# devbrd.net
KiCad netlist of a schematic drawn in EAGLE
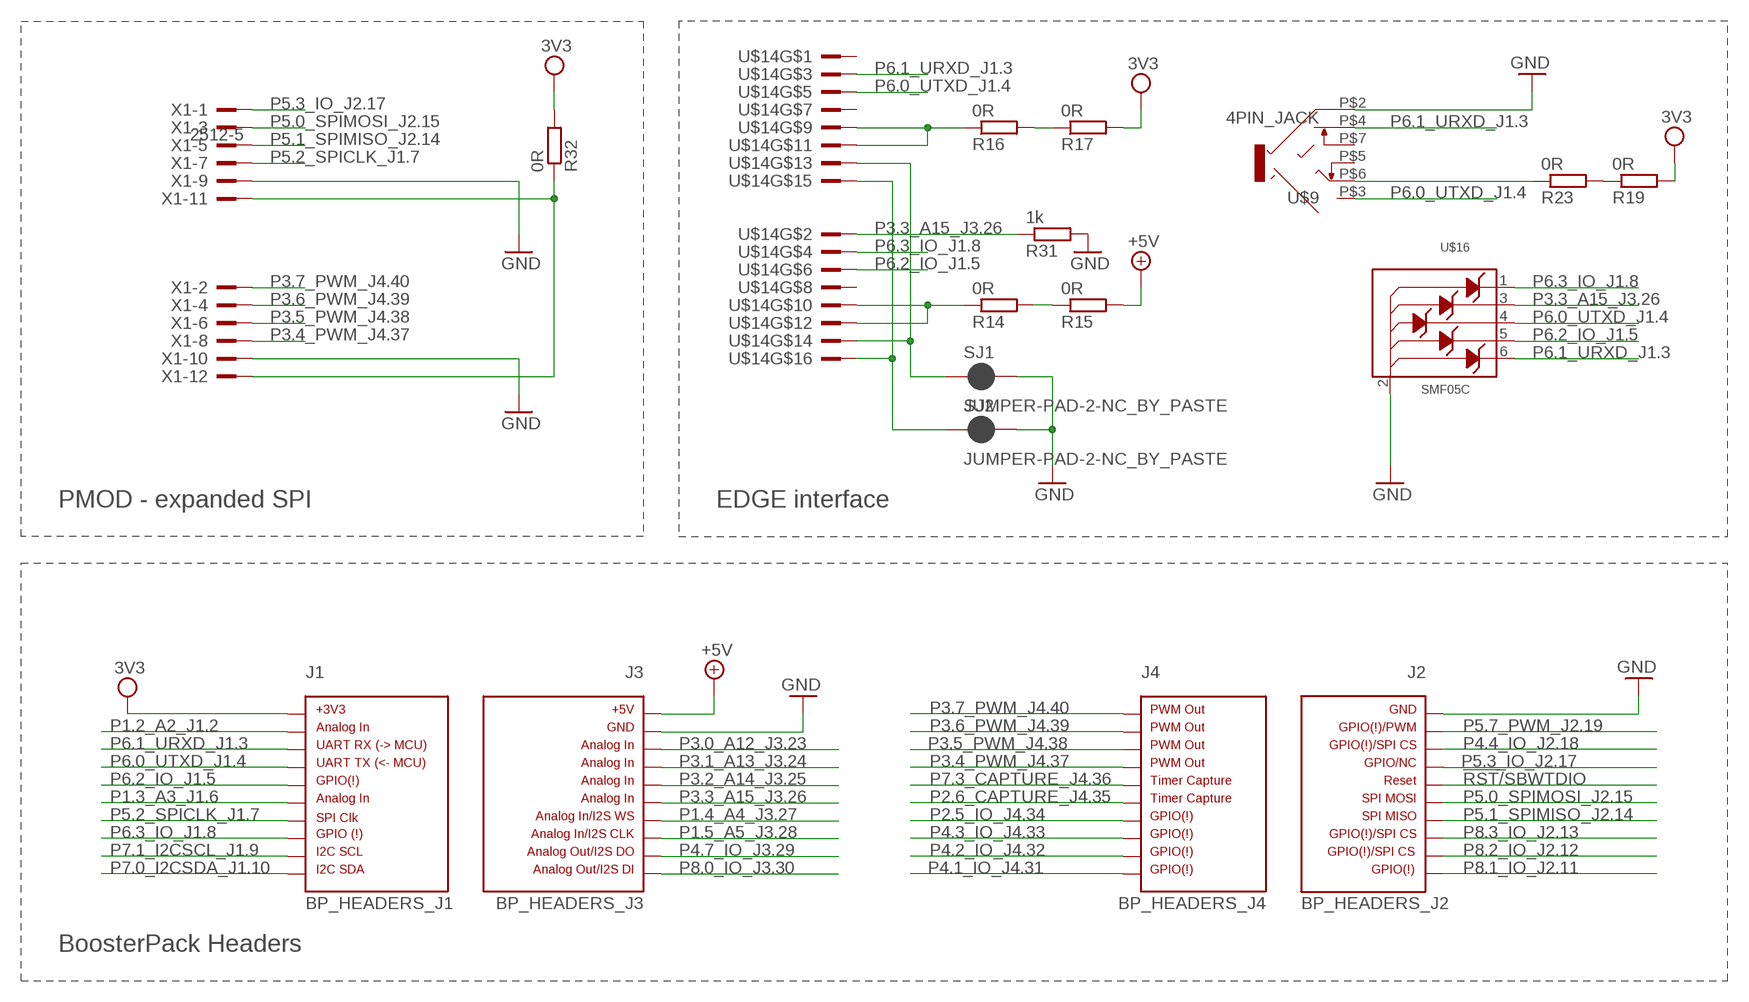
[diagram p0: schematic, sheet 1]
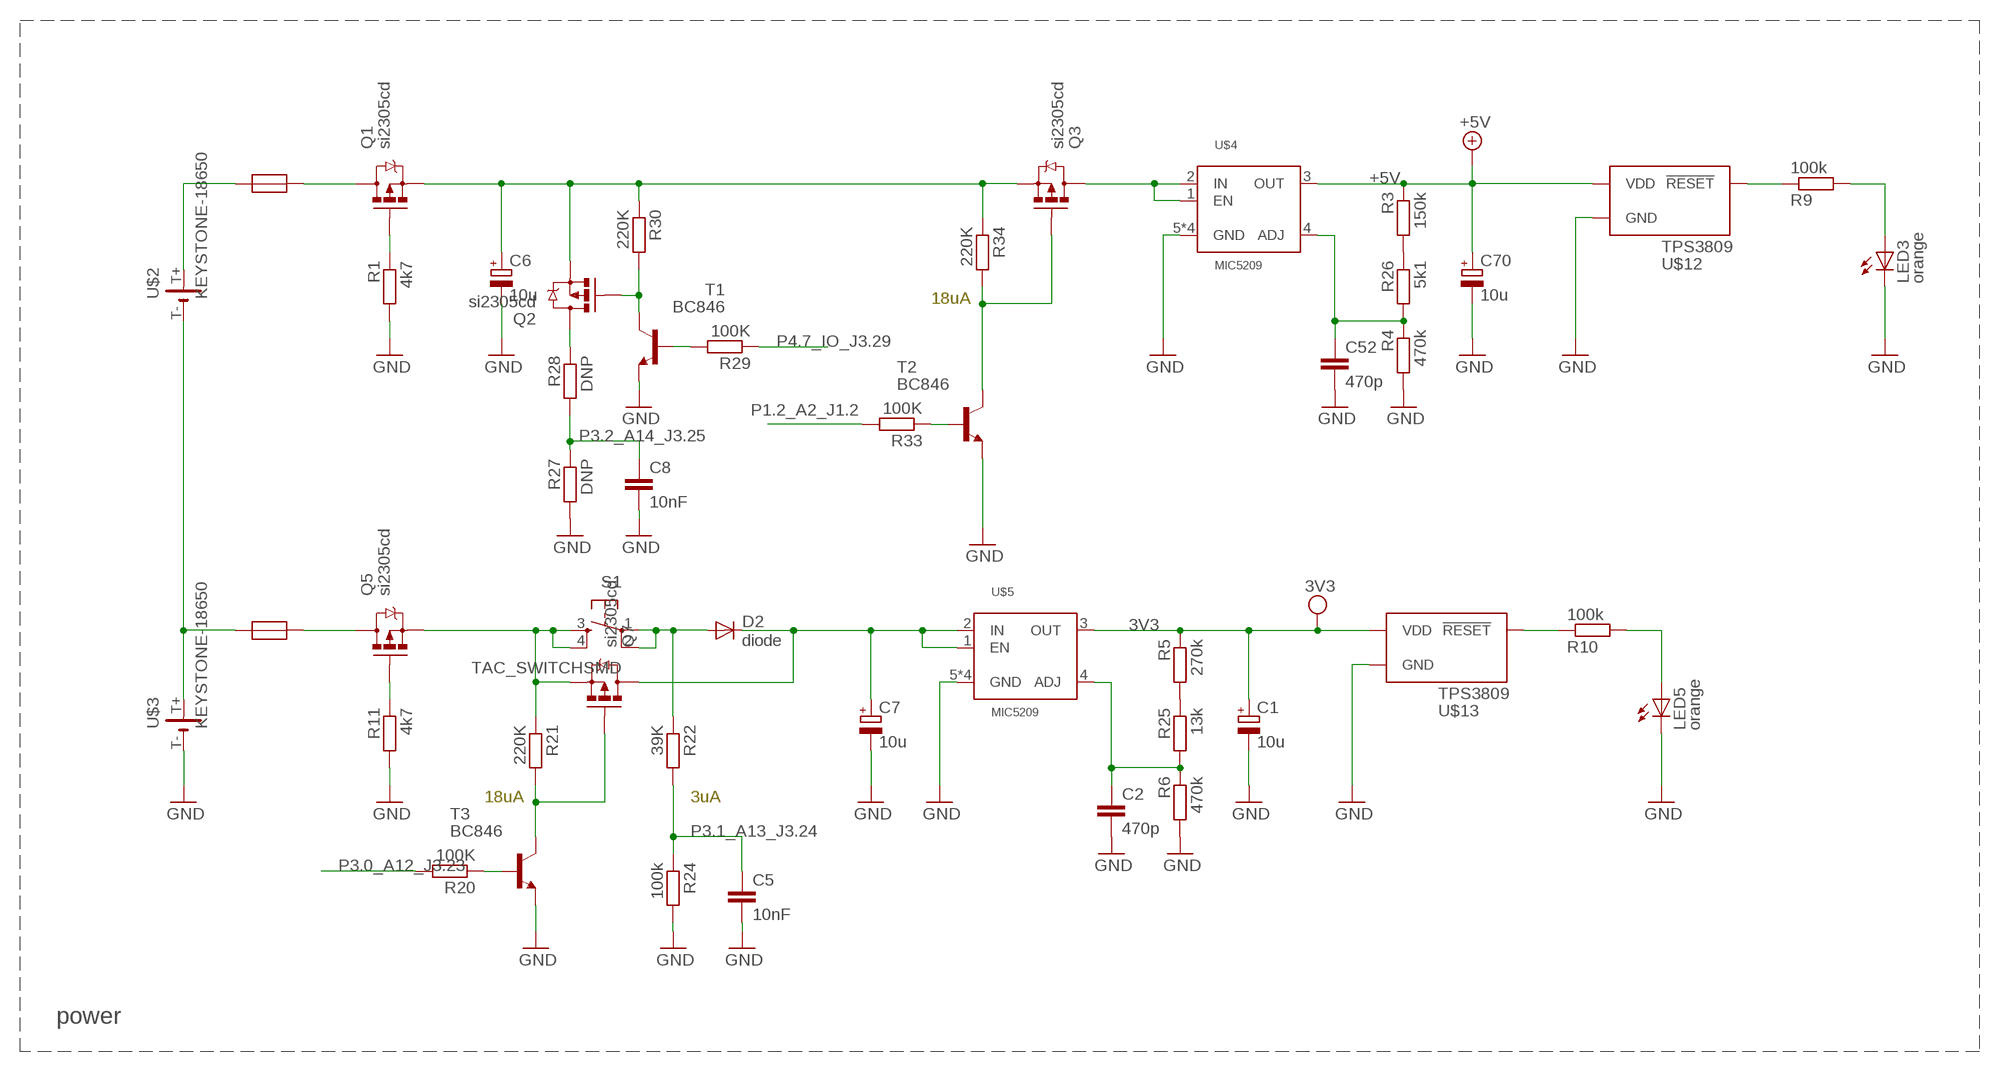
[diagram p1: schematic, sheet 2]
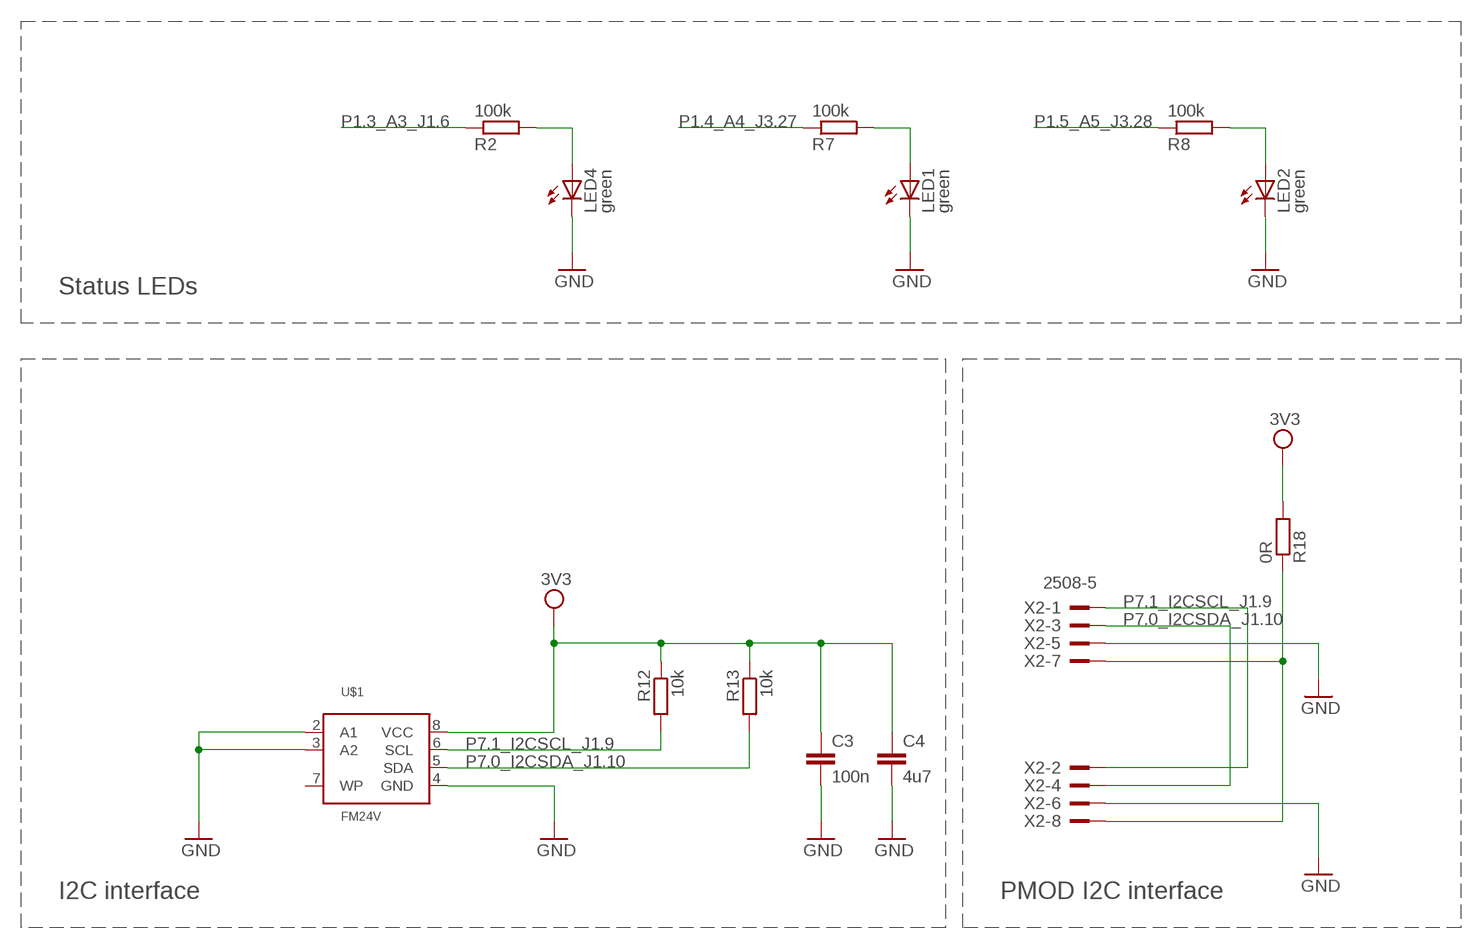
[diagram p2: schematic, sheet 3]

(export (version "E")
  (design (tool "Eeschema 10.0.6"))
  (components
    (comp (ref "C1")
      (value "10u")
      (footprint "eagle-import:153CLV-0405")
      (libsource (lib "eagle-import") (part "CPOL-EU153CLV-0405"))
    )
    (comp (ref "C2")
      (value "470p")
      (footprint "eagle-import:C0805")
      (libsource (lib "eagle-import") (part "C-EUC0805"))
    )
    (comp (ref "C5")
      (value "10nF")
      (footprint "eagle-import:C0805")
      (libsource (lib "eagle-import") (part "C-EUC0805"))
    )
    (comp (ref "C6")
      (value "10u")
      (footprint "eagle-import:153CLV-0405")
      (libsource (lib "eagle-import") (part "CPOL-EU153CLV-0405"))
    )
    (comp (ref "C7")
      (value "10u")
      (footprint "eagle-import:153CLV-0405")
      (libsource (lib "eagle-import") (part "CPOL-EU153CLV-0405"))
    )
    (comp (ref "C8")
      (value "10nF")
      (footprint "eagle-import:C0805")
      (libsource (lib "eagle-import") (part "C-EUC0805"))
    )
    (comp (ref "C52")
      (value "470p")
      (footprint "eagle-import:C0805")
      (libsource (lib "eagle-import") (part "C-EUC0805"))
    )
    (comp (ref "C70")
      (value "10u")
      (footprint "eagle-import:153CLV-0405")
      (libsource (lib "eagle-import") (part "CPOL-EU153CLV-0405"))
    )
    (comp (ref "D2")
      (value "diode")
      (footprint "eagle-import:SMA-DIODE")
      (libsource (lib "eagle-import") (part "DIODESMA"))
    )
    (comp (ref "LED3")
      (value "orange")
      (footprint "eagle-import:CHIPLED_0805")
      (libsource (lib "eagle-import") (part "LEDCHIPLED_0805"))
    )
    (comp (ref "LED5")
      (value "orange")
      (footprint "eagle-import:CHIPLED_0805")
      (libsource (lib "eagle-import") (part "LEDCHIPLED_0805"))
    )
    (comp (ref "Q1")
      (value "si2305cd")
      (footprint "eagle-import:SOT23-3_POWER")
      (libsource (lib "eagle-import") (part "MOSFET-PCHANNELSMD_POWER"))
    )
    (comp (ref "Q2")
      (value "si2305cd")
      (footprint "eagle-import:SOT23-3_POWER")
      (libsource (lib "eagle-import") (part "MOSFET-PCHANNELSMD_POWER"))
    )
    (comp (ref "Q3")
      (value "si2305cd")
      (footprint "eagle-import:SOT23-3_POWER")
      (libsource (lib "eagle-import") (part "MOSFET-PCHANNELSMD_POWER"))
    )
    (comp (ref "Q5")
      (value "si2305cd")
      (footprint "eagle-import:SOT23-3_POWER")
      (libsource (lib "eagle-import") (part "MOSFET-PCHANNELSMD_POWER"))
    )
    (comp (ref "Q7")
      (value "si2305cd")
      (footprint "eagle-import:SOT23-3_POWER")
      (libsource (lib "eagle-import") (part "MOSFET-PCHANNELSMD_POWER"))
    )
    (comp (ref "R1")
      (value "4k7")
      (footprint "eagle-import:R0805W")
      (libsource (lib "eagle-import") (part "R-EU_R0805W"))
    )
    (comp (ref "R3")
      (value "150k")
      (footprint "eagle-import:R0805W")
      (libsource (lib "eagle-import") (part "R-EU_R0805W"))
    )
    (comp (ref "R4")
      (value "470k")
      (footprint "eagle-import:R0805W")
      (libsource (lib "eagle-import") (part "R-EU_R0805W"))
    )
    (comp (ref "R5")
      (value "270k")
      (footprint "eagle-import:R0805W")
      (libsource (lib "eagle-import") (part "R-EU_R0805W"))
    )
    (comp (ref "R6")
      (value "470k")
      (footprint "eagle-import:R0805W")
      (libsource (lib "eagle-import") (part "R-EU_R0805W"))
    )
    (comp (ref "R9")
      (value "100k")
      (footprint "eagle-import:R0805W")
      (libsource (lib "eagle-import") (part "R-EU_R0805W"))
    )
    (comp (ref "R10")
      (value "100k")
      (footprint "eagle-import:R0805W")
      (libsource (lib "eagle-import") (part "R-EU_R0805W"))
    )
    (comp (ref "R11")
      (value "4k7")
      (footprint "eagle-import:R0805W")
      (libsource (lib "eagle-import") (part "R-EU_R0805W"))
    )
    (comp (ref "R20")
      (value "100K")
      (footprint "eagle-import:R0805W")
      (libsource (lib "eagle-import") (part "R-EU_R0805W"))
    )
    (comp (ref "R21")
      (value "220K")
      (footprint "eagle-import:R0805W")
      (libsource (lib "eagle-import") (part "R-EU_R0805W"))
    )
    (comp (ref "R22")
      (value "39K")
      (footprint "eagle-import:R0805W")
      (libsource (lib "eagle-import") (part "R-EU_R0805W"))
    )
    (comp (ref "R24")
      (value "100k")
      (footprint "eagle-import:R0805W")
      (libsource (lib "eagle-import") (part "R-EU_R0805W"))
    )
    (comp (ref "R25")
      (value "13k")
      (footprint "eagle-import:R0805W")
      (libsource (lib "eagle-import") (part "R-EU_R0805W"))
    )
    (comp (ref "R26")
      (value "5k1")
      (footprint "eagle-import:R0805W")
      (libsource (lib "eagle-import") (part "R-EU_R0805W"))
    )
    (comp (ref "R27")
      (value "DNP")
      (footprint "eagle-import:R0805W")
      (libsource (lib "eagle-import") (part "R-EU_R0805W"))
    )
    (comp (ref "R28")
      (value "DNP")
      (footprint "eagle-import:R0805W")
      (libsource (lib "eagle-import") (part "R-EU_R0805W"))
    )
    (comp (ref "R29")
      (value "100K")
      (footprint "eagle-import:R0805W")
      (libsource (lib "eagle-import") (part "R-EU_R0805W"))
    )
    (comp (ref "R30")
      (value "220K")
      (footprint "eagle-import:R0805W")
      (libsource (lib "eagle-import") (part "R-EU_R0805W"))
    )
    (comp (ref "R33")
      (value "100K")
      (footprint "eagle-import:R0805W")
      (libsource (lib "eagle-import") (part "R-EU_R0805W"))
    )
    (comp (ref "R34")
      (value "220K")
      (footprint "eagle-import:R0805W")
      (libsource (lib "eagle-import") (part "R-EU_R0805W"))
    )
    (comp (ref "S1")
      (value "TAC_SWITCHSMD")
      (footprint "eagle-import:TACTILE-SWITCH-SMD")
      (libsource (lib "eagle-import") (part "TAC_SWITCHSMD"))
    )
    (comp (ref "T1")
      (value "BC846")
      (footprint "eagle-import:SOT23")
      (libsource (lib "eagle-import") (part "BC846"))
    )
    (comp (ref "T2")
      (value "BC846")
      (footprint "eagle-import:SOT23")
      (libsource (lib "eagle-import") (part "BC846"))
    )
    (comp (ref "T3")
      (value "BC846")
      (footprint "eagle-import:SOT23")
      (libsource (lib "eagle-import") (part "BC846"))
    )
    (comp (ref "U$2")
      (value "KEYSTONE-18650")
      (footprint "eagle-import:KEYSTONE_COMBO_18650")
      (libsource (lib "eagle-import") (part "KEYSTONE-18650"))
    )
    (comp (ref "U$3")
      (value "KEYSTONE-18650")
      (footprint "eagle-import:KEYSTONE_COMBO_18650")
      (libsource (lib "eagle-import") (part "KEYSTONE-18650"))
    )
    (comp (ref "U$4")
      (value "MIC5209")
      (footprint "eagle-import:SO-08")
      (libsource (lib "eagle-import") (part "MIC5209"))
    )
    (comp (ref "U$5")
      (value "MIC5209")
      (footprint "eagle-import:SO-08")
      (libsource (lib "eagle-import") (part "MIC5209"))
    )
    (comp (ref "U$7")
      (value "RESETTABLE_0805")
      (footprint "eagle-import:0805W")
      (libsource (lib "eagle-import") (part "RESETTABLE_0805"))
    )
    (comp (ref "U$8")
      (value "RESETTABLE_0805")
      (footprint "eagle-import:0805W")
      (libsource (lib "eagle-import") (part "RESETTABLE_0805"))
    )
    (comp (ref "U$12")
      (value "TPS3809")
      (footprint "eagle-import:R_PDSO_G3")
      (libsource (lib "eagle-import") (part "TPS3809"))
    )
    (comp (ref "U$13")
      (value "TPS3809")
      (footprint "eagle-import:R_PDSO_G3")
      (libsource (lib "eagle-import") (part "TPS3809"))
    )
    (comp (ref "J1")
      (value "BP_HEADERS_J1")
      (footprint "eagle-import:J1")
      (libsource (lib "eagle-import") (part "BP_HEADERS_J1"))
    )
    (comp (ref "J2")
      (value "BP_HEADERS_J2")
      (footprint "eagle-import:J2")
      (libsource (lib "eagle-import") (part "BP_HEADERS_J2"))
    )
    (comp (ref "J3")
      (value "BP_HEADERS_J3")
      (footprint "eagle-import:J3")
      (libsource (lib "eagle-import") (part "BP_HEADERS_J3"))
    )
    (comp (ref "J4")
      (value "BP_HEADERS_J4")
      (footprint "eagle-import:J4")
      (libsource (lib "eagle-import") (part "BP_HEADERS_J4"))
    )
    (comp (ref "R14")
      (value "0R")
      (footprint "eagle-import:R0805W")
      (libsource (lib "eagle-import") (part "R-EU_R0805W"))
    )
    (comp (ref "R15")
      (value "0R")
      (footprint "eagle-import:0204V")
      (libsource (lib "eagle-import") (part "R-EU_0204/2V"))
    )
    (comp (ref "R16")
      (value "0R")
      (footprint "eagle-import:R0805W")
      (libsource (lib "eagle-import") (part "R-EU_R0805W"))
    )
    (comp (ref "R17")
      (value "0R")
      (footprint "eagle-import:0204V")
      (libsource (lib "eagle-import") (part "R-EU_0204/2V"))
    )
    (comp (ref "R19")
      (value "0R")
      (footprint "eagle-import:0204V")
      (libsource (lib "eagle-import") (part "R-EU_0204/2V"))
    )
    (comp (ref "R23")
      (value "0R")
      (footprint "eagle-import:R0805W")
      (libsource (lib "eagle-import") (part "R-EU_R0805W"))
    )
    (comp (ref "R31")
      (value "1k")
      (footprint "eagle-import:R0805W")
      (libsource (lib "eagle-import") (part "R-EU_R0805W"))
    )
    (comp (ref "R32")
      (value "0R")
      (footprint "eagle-import:0204V")
      (libsource (lib "eagle-import") (part "R-EU_0204/2V"))
    )
    (comp (ref "SJ1")
      (value "JUMPER-PAD-2-NC_BY_PASTE")
      (footprint "eagle-import:PAD-JUMPER-2-NC_BY_PASTE_YES_SILK")
      (libsource (lib "eagle-import") (part "JUMPER-PAD-2-NC_BY_PASTE"))
    )
    (comp (ref "SJ2")
      (value "JUMPER-PAD-2-NC_BY_PASTE")
      (footprint "eagle-import:PAD-JUMPER-2-NC_BY_PASTE_YES_SILK")
      (libsource (lib "eagle-import") (part "JUMPER-PAD-2-NC_BY_PASTE"))
    )
    (comp (ref "U$9")
      (value "4PIN_JACK")
      (footprint "eagle-import:4PIN_JACK")
      (libsource (lib "eagle-import") (part "4PIN_JACK"))
    )
    (comp (ref "U$14")
      (value "2516-")
      (footprint "eagle-import:PAK100_2500-5-16")
      (libsource (lib "eagle-import") (part "2516-"))
    )
    (comp (ref "U$16")
      (value "SMF05C")
      (footprint "eagle-import:SC-88")
      (libsource (lib "eagle-import") (part "SMF05C"))
    )
    (comp (ref "X1")
      (value "2512-5")
      (footprint "eagle-import:PAK100_2500-5-12")
      (fields (field (name "MPN") "N2514-5002RB"))
      (libsource (lib "eagle-import") (part "2512-5"))
    )
    (comp (ref "C3")
      (value "100n")
      (footprint "eagle-import:C0805")
      (libsource (lib "eagle-import") (part "C-EUC0805"))
    )
    (comp (ref "C4")
      (value "4u7")
      (footprint "eagle-import:C0805")
      (libsource (lib "eagle-import") (part "C-EUC0805"))
    )
    (comp (ref "LED1")
      (value "green")
      (footprint "eagle-import:CHIPLED_0805")
      (libsource (lib "eagle-import") (part "LEDCHIPLED_0805"))
    )
    (comp (ref "LED2")
      (value "green")
      (footprint "eagle-import:CHIPLED_0805")
      (libsource (lib "eagle-import") (part "LEDCHIPLED_0805"))
    )
    (comp (ref "LED4")
      (value "green")
      (footprint "eagle-import:CHIPLED_0805")
      (libsource (lib "eagle-import") (part "LEDCHIPLED_0805"))
    )
    (comp (ref "R2")
      (value "100k")
      (footprint "eagle-import:R0805W")
      (libsource (lib "eagle-import") (part "R-EU_R0805W"))
    )
    (comp (ref "R7")
      (value "100k")
      (footprint "eagle-import:R0805W")
      (libsource (lib "eagle-import") (part "R-EU_R0805W"))
    )
    (comp (ref "R8")
      (value "100k")
      (footprint "eagle-import:R0805W")
      (libsource (lib "eagle-import") (part "R-EU_R0805W"))
    )
    (comp (ref "R12")
      (value "10k")
      (footprint "eagle-import:R0805W")
      (libsource (lib "eagle-import") (part "R-EU_R0805W"))
    )
    (comp (ref "R13")
      (value "10k")
      (footprint "eagle-import:R0805W")
      (libsource (lib "eagle-import") (part "R-EU_R0805W"))
    )
    (comp (ref "R18")
      (value "0R")
      (footprint "eagle-import:0204V")
      (libsource (lib "eagle-import") (part "R-EU_0204/2V"))
    )
    (comp (ref "U$1")
      (value "FM24V")
      (footprint "eagle-import:SO-08")
      (libsource (lib "eagle-import") (part "FM24V"))
    )
    (comp (ref "X2")
      (value "2508-5")
      (footprint "eagle-import:PAK100_2500-5-08")
      (libsource (lib "eagle-import") (part "2508-5"))
    )
  )
  (nets
    (net (code "1") (name "+5V") (class "Default")
      (node (ref "C70") (pin "+") (pinfunction "+_+") (pintype "passive"))
      (node (ref "J3") (pin "21") (pinfunction "21_21") (pintype "bidirectional"))
      (node (ref "R15") (pin "2") (pinfunction "2_2") (pintype "passive"))
      (node (ref "R3") (pin "1") (pinfunction "1_1") (pintype "passive"))
      (node (ref "U$12") (pin "P$3") (pinfunction "VDD_P$3") (pintype "bidirectional"))
      (node (ref "U$4") (pin "3") (pinfunction "OUT_3") (pintype "bidirectional"))
    )
    (net (code "2") (name "3V3") (class "Default")
      (node (ref "C1") (pin "+") (pinfunction "+_+") (pintype "passive"))
      (node (ref "C3") (pin "1") (pinfunction "1_1") (pintype "passive"))
      (node (ref "C4") (pin "1") (pinfunction "1_1") (pintype "passive"))
      (node (ref "J1") (pin "1") (pinfunction "1_1") (pintype "bidirectional"))
      (node (ref "R12") (pin "1") (pinfunction "1_1") (pintype "passive"))
      (node (ref "R13") (pin "1") (pinfunction "1_1") (pintype "passive"))
      (node (ref "R17") (pin "2") (pinfunction "2_2") (pintype "passive"))
      (node (ref "R18") (pin "2") (pinfunction "2_2") (pintype "passive"))
      (node (ref "R19") (pin "2") (pinfunction "2_2") (pintype "passive"))
      (node (ref "R32") (pin "2") (pinfunction "2_2") (pintype "passive"))
      (node (ref "R5") (pin "1") (pinfunction "1_1") (pintype "passive"))
      (node (ref "U$1") (pin "8") (pinfunction "VCC_8") (pintype "bidirectional"))
      (node (ref "U$13") (pin "P$3") (pinfunction "VDD_P$3") (pintype "bidirectional"))
      (node (ref "U$5") (pin "3") (pinfunction "OUT_3") (pintype "bidirectional"))
    )
    (net (code "3") (name "GND") (class "Default")
      (node (ref "C1") (pin "-") (pinfunction "-_-") (pintype "passive"))
      (node (ref "C2") (pin "2") (pinfunction "2_2") (pintype "passive"))
      (node (ref "C3") (pin "2") (pinfunction "2_2") (pintype "passive"))
      (node (ref "C4") (pin "2") (pinfunction "2_2") (pintype "passive"))
      (node (ref "C5") (pin "2") (pinfunction "2_2") (pintype "passive"))
      (node (ref "C52") (pin "2") (pinfunction "2_2") (pintype "passive"))
      (node (ref "C6") (pin "-") (pinfunction "-_-") (pintype "passive"))
      (node (ref "C7") (pin "-") (pinfunction "-_-") (pintype "passive"))
      (node (ref "C70") (pin "-") (pinfunction "-_-") (pintype "passive"))
      (node (ref "C8") (pin "2") (pinfunction "2_2") (pintype "passive"))
      (node (ref "J2") (pin "20") (pinfunction "20_20") (pintype "bidirectional"))
      (node (ref "J3") (pin "22") (pinfunction "22_22") (pintype "bidirectional"))
      (node (ref "LED1") (pin "C") (pinfunction "C_C") (pintype "passive"))
      (node (ref "LED2") (pin "C") (pinfunction "C_C") (pintype "passive"))
      (node (ref "LED3") (pin "C") (pinfunction "C_C") (pintype "passive"))
      (node (ref "LED4") (pin "C") (pinfunction "C_C") (pintype "passive"))
      (node (ref "LED5") (pin "C") (pinfunction "C_C") (pintype "passive"))
      (node (ref "R1") (pin "2") (pinfunction "2_2") (pintype "passive"))
      (node (ref "R11") (pin "2") (pinfunction "2_2") (pintype "passive"))
      (node (ref "R24") (pin "2") (pinfunction "2_2") (pintype "passive"))
      (node (ref "R27") (pin "2") (pinfunction "2_2") (pintype "passive"))
      (node (ref "R31") (pin "2") (pinfunction "2_2") (pintype "passive"))
      (node (ref "R4") (pin "2") (pinfunction "2_2") (pintype "passive"))
      (node (ref "R6") (pin "2") (pinfunction "2_2") (pintype "passive"))
      (node (ref "SJ1") (pin "2") (pinfunction "2_2") (pintype "passive"))
      (node (ref "SJ2") (pin "2") (pinfunction "2_2") (pintype "passive"))
      (node (ref "T1") (pin "2") (pinfunction "E_2") (pintype "passive"))
      (node (ref "T2") (pin "2") (pinfunction "E_2") (pintype "passive"))
      (node (ref "T3") (pin "2") (pinfunction "E_2") (pintype "passive"))
      (node (ref "U$1") (pin "2") (pinfunction "A1_2") (pintype "bidirectional"))
      (node (ref "U$1") (pin "3") (pinfunction "A2_3") (pintype "bidirectional"))
      (node (ref "U$1") (pin "4") (pinfunction "GND_4") (pintype "bidirectional"))
      (node (ref "U$12") (pin "P$1") (pinfunction "GND_P$1") (pintype "bidirectional"))
      (node (ref "U$13") (pin "P$1") (pinfunction "GND_P$1") (pintype "bidirectional"))
      (node (ref "U$16") (pin "2") (pinfunction "ANODE_2") (pintype "passive"))
      (node (ref "U$3") (pin "T-") (pinfunction "-_T-") (pintype "passive"))
      (node (ref "U$4") (pin "5") (pinfunction "GND_5") (pintype "bidirectional"))
      (node (ref "U$4") (pin "6") (pinfunction "GND_6") (pintype "bidirectional"))
      (node (ref "U$4") (pin "7") (pinfunction "GND_7") (pintype "bidirectional"))
      (node (ref "U$4") (pin "8") (pinfunction "GND_8") (pintype "bidirectional"))
      (node (ref "U$5") (pin "5") (pinfunction "GND_5") (pintype "bidirectional"))
      (node (ref "U$5") (pin "6") (pinfunction "GND_6") (pintype "bidirectional"))
      (node (ref "U$5") (pin "7") (pinfunction "GND_7") (pintype "bidirectional"))
      (node (ref "U$5") (pin "8") (pinfunction "GND_8") (pintype "bidirectional"))
      (node (ref "U$9") (pin "P$2") (pinfunction "2_P$2") (pintype "passive"))
      (node (ref "X1") (pin "10") (pinfunction "KL_10") (pintype "passive"))
      (node (ref "X1") (pin "9") (pinfunction "KL_9") (pintype "passive"))
      (node (ref "X2") (pin "5") (pinfunction "KL_5") (pintype "passive"))
      (node (ref "X2") (pin "6") (pinfunction "KL_6") (pintype "passive"))
    )
    (net (code "4") (name "Net-(D2-PadA)") (class "Default")
      (node (ref "D2") (pin "A") (pinfunction "A_A") (pintype "passive"))
      (node (ref "R22") (pin "1") (pinfunction "1_1") (pintype "passive"))
      (node (ref "S1") (pin "1") (pinfunction "1_1") (pintype "passive"))
      (node (ref "S1") (pin "2") (pinfunction "2_2") (pintype "passive"))
    )
    (net (code "5") (name "Net-(LED1-PadA)") (class "Default")
      (node (ref "LED1") (pin "A") (pinfunction "A_A") (pintype "passive"))
      (node (ref "R7") (pin "2") (pinfunction "2_2") (pintype "passive"))
    )
    (net (code "6") (name "Net-(LED2-PadA)") (class "Default")
      (node (ref "LED2") (pin "A") (pinfunction "A_A") (pintype "passive"))
      (node (ref "R8") (pin "2") (pinfunction "2_2") (pintype "passive"))
    )
    (net (code "7") (name "Net-(LED3-PadA)") (class "Default")
      (node (ref "LED3") (pin "A") (pinfunction "A_A") (pintype "passive"))
      (node (ref "R9") (pin "2") (pinfunction "2_2") (pintype "passive"))
    )
    (net (code "8") (name "Net-(LED4-PadA)") (class "Default")
      (node (ref "LED4") (pin "A") (pinfunction "A_A") (pintype "passive"))
      (node (ref "R2") (pin "2") (pinfunction "2_2") (pintype "passive"))
    )
    (net (code "9") (name "Net-(LED5-PadA)") (class "Default")
      (node (ref "LED5") (pin "A") (pinfunction "A_A") (pintype "passive"))
      (node (ref "R10") (pin "2") (pinfunction "2_2") (pintype "passive"))
    )
    (net (code "10") (name "Net-(Q1-D)") (class "Default")
      (node (ref "Q1") (pin "3") (pinfunction "D_3") (pintype "passive"))
      (node (ref "U$7") (pin "2") (pinfunction "P$2_2") (pintype "bidirectional"))
    )
    (net (code "11") (name "Net-(Q1-G)") (class "Default")
      (node (ref "Q1") (pin "1") (pinfunction "G_1") (pintype "passive"))
      (node (ref "R1") (pin "1") (pinfunction "1_1") (pintype "passive"))
    )
    (net (code "12") (name "Net-(Q1-S)") (class "Default")
      (node (ref "C6") (pin "+") (pinfunction "+_+") (pintype "passive"))
      (node (ref "Q1") (pin "2") (pinfunction "S_2") (pintype "passive"))
      (node (ref "Q2") (pin "2") (pinfunction "S_2") (pintype "passive"))
      (node (ref "Q3") (pin "2") (pinfunction "S_2") (pintype "passive"))
      (node (ref "R30") (pin "1") (pinfunction "1_1") (pintype "passive"))
      (node (ref "R34") (pin "1") (pinfunction "1_1") (pintype "passive"))
    )
    (net (code "13") (name "Net-(Q2-D)") (class "Default")
      (node (ref "Q2") (pin "3") (pinfunction "D_3") (pintype "passive"))
      (node (ref "R28") (pin "1") (pinfunction "1_1") (pintype "passive"))
    )
    (net (code "14") (name "Net-(Q2-G)") (class "Default")
      (node (ref "Q2") (pin "1") (pinfunction "G_1") (pintype "passive"))
      (node (ref "R30") (pin "2") (pinfunction "2_2") (pintype "passive"))
      (node (ref "T1") (pin "3") (pinfunction "C_3") (pintype "passive"))
    )
    (net (code "15") (name "Net-(Q3-D)") (class "Default")
      (node (ref "Q3") (pin "3") (pinfunction "D_3") (pintype "passive"))
      (node (ref "U$4") (pin "1") (pinfunction "EN_1") (pintype "bidirectional"))
      (node (ref "U$4") (pin "2") (pinfunction "IN_2") (pintype "bidirectional"))
    )
    (net (code "16") (name "Net-(Q3-G)") (class "Default")
      (node (ref "Q3") (pin "1") (pinfunction "G_1") (pintype "passive"))
      (node (ref "R34") (pin "2") (pinfunction "2_2") (pintype "passive"))
      (node (ref "T2") (pin "3") (pinfunction "C_3") (pintype "passive"))
    )
    (net (code "17") (name "Net-(Q5-D)") (class "Default")
      (node (ref "Q5") (pin "3") (pinfunction "D_3") (pintype "passive"))
      (node (ref "U$8") (pin "2") (pinfunction "P$2_2") (pintype "bidirectional"))
    )
    (net (code "18") (name "Net-(Q5-G)") (class "Default")
      (node (ref "Q5") (pin "1") (pinfunction "G_1") (pintype "passive"))
      (node (ref "R11") (pin "1") (pinfunction "1_1") (pintype "passive"))
    )
    (net (code "19") (name "Net-(Q5-S)") (class "Default")
      (node (ref "Q5") (pin "2") (pinfunction "S_2") (pintype "passive"))
      (node (ref "Q7") (pin "2") (pinfunction "S_2") (pintype "passive"))
      (node (ref "R21") (pin "1") (pinfunction "1_1") (pintype "passive"))
      (node (ref "S1") (pin "3") (pinfunction "3_3") (pintype "passive"))
      (node (ref "S1") (pin "4") (pinfunction "4_4") (pintype "passive"))
    )
    (net (code "20") (name "Net-(Q7-D)") (class "Default")
      (node (ref "C7") (pin "+") (pinfunction "+_+") (pintype "passive"))
      (node (ref "D2") (pin "C") (pinfunction "C_C") (pintype "passive"))
      (node (ref "Q7") (pin "3") (pinfunction "D_3") (pintype "passive"))
      (node (ref "U$5") (pin "1") (pinfunction "EN_1") (pintype "bidirectional"))
      (node (ref "U$5") (pin "2") (pinfunction "IN_2") (pintype "bidirectional"))
    )
    (net (code "21") (name "Net-(Q7-G)") (class "Default")
      (node (ref "Q7") (pin "1") (pinfunction "G_1") (pintype "passive"))
      (node (ref "R21") (pin "2") (pinfunction "2_2") (pintype "passive"))
      (node (ref "T3") (pin "3") (pinfunction "C_3") (pintype "passive"))
    )
    (net (code "22") (name "Net-(R14-Pad2)") (class "Default")
      (node (ref "R14") (pin "2") (pinfunction "2_2") (pintype "passive"))
      (node (ref "R15") (pin "1") (pinfunction "1_1") (pintype "passive"))
    )
    (net (code "23") (name "Net-(R16-Pad2)") (class "Default")
      (node (ref "R16") (pin "2") (pinfunction "2_2") (pintype "passive"))
      (node (ref "R17") (pin "1") (pinfunction "1_1") (pintype "passive"))
    )
    (net (code "24") (name "Net-(R19-Pad1)") (class "Default")
      (node (ref "R19") (pin "1") (pinfunction "1_1") (pintype "passive"))
      (node (ref "R23") (pin "2") (pinfunction "2_2") (pintype "passive"))
    )
    (net (code "25") (name "Net-(R25-Pad1)") (class "Default")
      (node (ref "R25") (pin "1") (pinfunction "1_1") (pintype "passive"))
      (node (ref "R5") (pin "2") (pinfunction "2_2") (pintype "passive"))
    )
    (net (code "26") (name "Net-(R26-Pad1)") (class "Default")
      (node (ref "R26") (pin "1") (pinfunction "1_1") (pintype "passive"))
      (node (ref "R3") (pin "2") (pinfunction "2_2") (pintype "passive"))
    )
    (net (code "27") (name "Net-(T1-B)") (class "Default")
      (node (ref "R29") (pin "2") (pinfunction "2_2") (pintype "passive"))
      (node (ref "T1") (pin "1") (pinfunction "B_1") (pintype "passive"))
    )
    (net (code "28") (name "Net-(T2-B)") (class "Default")
      (node (ref "R33") (pin "1") (pinfunction "1_1") (pintype "passive"))
      (node (ref "T2") (pin "1") (pinfunction "B_1") (pintype "passive"))
    )
    (net (code "29") (name "Net-(T3-B)") (class "Default")
      (node (ref "R20") (pin "1") (pinfunction "1_1") (pintype "passive"))
      (node (ref "T3") (pin "1") (pinfunction "B_1") (pintype "passive"))
    )
    (net (code "30") (name "Net-(U$2-+)") (class "Default")
      (node (ref "U$2") (pin "T+") (pinfunction "+_T+") (pintype "passive"))
      (node (ref "U$7") (pin "1") (pinfunction "P$1_1") (pintype "bidirectional"))
    )
    (net (code "31") (name "Net-(U$2--)") (class "Default")
      (node (ref "U$2") (pin "T-") (pinfunction "-_T-") (pintype "passive"))
      (node (ref "U$3") (pin "T+") (pinfunction "+_T+") (pintype "passive"))
      (node (ref "U$8") (pin "1") (pinfunction "P$1_1") (pintype "bidirectional"))
    )
    (net (code "32") (name "Net-(U$4-ADJ)") (class "Default")
      (node (ref "C52") (pin "1") (pinfunction "1_1") (pintype "passive"))
      (node (ref "R26") (pin "2") (pinfunction "2_2") (pintype "passive"))
      (node (ref "R4") (pin "1") (pinfunction "1_1") (pintype "passive"))
      (node (ref "U$4") (pin "4") (pinfunction "ADJ_4") (pintype "bidirectional"))
    )
    (net (code "33") (name "Net-(U$5-ADJ)") (class "Default")
      (node (ref "C2") (pin "1") (pinfunction "1_1") (pintype "passive"))
      (node (ref "R25") (pin "2") (pinfunction "2_2") (pintype "passive"))
      (node (ref "R6") (pin "1") (pinfunction "1_1") (pintype "passive"))
      (node (ref "U$5") (pin "4") (pinfunction "ADJ_4") (pintype "bidirectional"))
    )
    (net (code "34") (name "Net-(U$9-6)") (class "Default")
      (node (ref "R23") (pin "1") (pinfunction "1_1") (pintype "passive"))
      (node (ref "U$9") (pin "P$6") (pinfunction "6_P$6") (pintype "passive"))
    )
    (net (code "35") (name "Net-(U$12-~{RESET})") (class "Default")
      (node (ref "R9") (pin "1") (pinfunction "1_1") (pintype "passive"))
      (node (ref "U$12") (pin "P$2") (pinfunction "~{RESET}_P$2") (pintype "bidirectional"))
    )
    (net (code "36") (name "Net-(U$13-~{RESET})") (class "Default")
      (node (ref "R10") (pin "1") (pinfunction "1_1") (pintype "passive"))
      (node (ref "U$13") (pin "P$2") (pinfunction "~{RESET}_P$2") (pintype "bidirectional"))
    )
    (net (code "37") (name "Net-(U$14B-KL)") (class "Default")
      (node (ref "R14") (pin "1") (pinfunction "1_1") (pintype "passive"))
      (node (ref "U$14") (pin "10") (pinfunction "KL_10") (pintype "passive"))
      (node (ref "U$14") (pin "12") (pinfunction "KL_12") (pintype "passive"))
    )
    (net (code "38") (name "Net-(U$14C-KL)") (class "Default")
      (node (ref "R16") (pin "1") (pinfunction "1_1") (pintype "passive"))
      (node (ref "U$14") (pin "11") (pinfunction "KL_11") (pintype "passive"))
      (node (ref "U$14") (pin "9") (pinfunction "KL_9") (pintype "passive"))
    )
    (net (code "39") (name "Net-(U$14E-KL)") (class "Default")
      (node (ref "SJ1") (pin "1") (pinfunction "1_1") (pintype "passive"))
      (node (ref "U$14") (pin "13") (pinfunction "KL_13") (pintype "passive"))
      (node (ref "U$14") (pin "14") (pinfunction "KL_14") (pintype "passive"))
    )
    (net (code "40") (name "Net-(U$14G-KL)") (class "Default")
      (node (ref "SJ2") (pin "1") (pinfunction "1_1") (pintype "passive"))
      (node (ref "U$14") (pin "15") (pinfunction "KL_15") (pintype "passive"))
      (node (ref "U$14") (pin "16") (pinfunction "KL_16") (pintype "passive"))
    )
    (net (code "41") (name "Net-(X1C-KL)") (class "Default")
      (node (ref "R32") (pin "1") (pinfunction "1_1") (pintype "passive"))
      (node (ref "X1") (pin "11") (pinfunction "KL_11") (pintype "passive"))
      (node (ref "X1") (pin "12") (pinfunction "KL_12") (pintype "passive"))
    )
    (net (code "42") (name "Net-(X2G-KL)") (class "Default")
      (node (ref "R18") (pin "1") (pinfunction "1_1") (pintype "passive"))
      (node (ref "X2") (pin "7") (pinfunction "KL_7") (pintype "passive"))
      (node (ref "X2") (pin "8") (pinfunction "KL_8") (pintype "passive"))
    )
    (net (code "43") (name "P1.2_A2_J1.2") (class "Default")
      (node (ref "J1") (pin "2") (pinfunction "2_2") (pintype "bidirectional"))
      (node (ref "R33") (pin "2") (pinfunction "2_2") (pintype "passive"))
    )
    (net (code "44") (name "P1.3_A3_J1.6") (class "Default")
      (node (ref "J1") (pin "6") (pinfunction "6_6") (pintype "bidirectional"))
      (node (ref "R2") (pin "1") (pinfunction "1_1") (pintype "passive"))
    )
    (net (code "45") (name "P1.4_A4_J3.27") (class "Default")
      (node (ref "J3") (pin "27") (pinfunction "27_27") (pintype "bidirectional"))
      (node (ref "R7") (pin "1") (pinfunction "1_1") (pintype "passive"))
    )
    (net (code "46") (name "P1.5_A5_J3.28") (class "Default")
      (node (ref "J3") (pin "28") (pinfunction "28_28") (pintype "bidirectional"))
      (node (ref "R8") (pin "1") (pinfunction "1_1") (pintype "passive"))
    )
    (net (code "47") (name "P2.5_IO_J4.34") (class "Default")
      (node (ref "J4") (pin "34") (pinfunction "34_34") (pintype "bidirectional"))
    )
    (net (code "48") (name "P2.6_CAPTURE_J4.35") (class "Default")
      (node (ref "J4") (pin "35") (pinfunction "35_35") (pintype "bidirectional"))
    )
    (net (code "49") (name "P3.0_A12_J3.23") (class "Default")
      (node (ref "J3") (pin "23") (pinfunction "23_23") (pintype "bidirectional"))
      (node (ref "R20") (pin "2") (pinfunction "2_2") (pintype "passive"))
    )
    (net (code "50") (name "P3.1_A13_J3.24") (class "Default")
      (node (ref "C5") (pin "1") (pinfunction "1_1") (pintype "passive"))
      (node (ref "J3") (pin "24") (pinfunction "24_24") (pintype "bidirectional"))
      (node (ref "R22") (pin "2") (pinfunction "2_2") (pintype "passive"))
      (node (ref "R24") (pin "1") (pinfunction "1_1") (pintype "passive"))
    )
    (net (code "51") (name "P3.2_A14_J3.25") (class "Default")
      (node (ref "C8") (pin "1") (pinfunction "1_1") (pintype "passive"))
      (node (ref "J3") (pin "25") (pinfunction "25_25") (pintype "bidirectional"))
      (node (ref "R27") (pin "1") (pinfunction "1_1") (pintype "passive"))
      (node (ref "R28") (pin "2") (pinfunction "2_2") (pintype "passive"))
    )
    (net (code "52") (name "P3.3_A15_J3.26") (class "Default")
      (node (ref "J3") (pin "26") (pinfunction "26_26") (pintype "bidirectional"))
      (node (ref "R31") (pin "1") (pinfunction "1_1") (pintype "passive"))
      (node (ref "U$14") (pin "2") (pinfunction "KL_2") (pintype "passive"))
      (node (ref "U$16") (pin "3") (pinfunction "CATODE2_3") (pintype "passive"))
    )
    (net (code "53") (name "P3.4_PWM_J4.37") (class "Default")
      (node (ref "J4") (pin "37") (pinfunction "37_37") (pintype "bidirectional"))
      (node (ref "X1") (pin "8") (pinfunction "KL_8") (pintype "passive"))
    )
    (net (code "54") (name "P3.5_PWM_J4.38") (class "Default")
      (node (ref "J4") (pin "38") (pinfunction "38_38") (pintype "bidirectional"))
      (node (ref "X1") (pin "6") (pinfunction "KL_6") (pintype "passive"))
    )
    (net (code "55") (name "P3.6_PWM_J4.39") (class "Default")
      (node (ref "J4") (pin "39") (pinfunction "39_39") (pintype "bidirectional"))
      (node (ref "X1") (pin "4") (pinfunction "KL_4") (pintype "passive"))
    )
    (net (code "56") (name "P3.7_PWM_J4.40") (class "Default")
      (node (ref "J4") (pin "40") (pinfunction "40_40") (pintype "bidirectional"))
      (node (ref "X1") (pin "2") (pinfunction "KL_2") (pintype "passive"))
    )
    (net (code "57") (name "P4.1_IO_J4.31") (class "Default")
      (node (ref "J4") (pin "31") (pinfunction "31_31") (pintype "bidirectional"))
    )
    (net (code "58") (name "P4.2_IO_J4.32") (class "Default")
      (node (ref "J4") (pin "32") (pinfunction "32_32") (pintype "bidirectional"))
    )
    (net (code "59") (name "P4.3_IO_J4.33") (class "Default")
      (node (ref "J4") (pin "33") (pinfunction "33_33") (pintype "bidirectional"))
    )
    (net (code "60") (name "P4.4_IO_J2.18") (class "Default")
      (node (ref "J2") (pin "18") (pinfunction "18_18") (pintype "bidirectional"))
    )
    (net (code "61") (name "P4.7_IO_J3.29") (class "Default")
      (node (ref "J3") (pin "29") (pinfunction "29_29") (pintype "bidirectional"))
      (node (ref "R29") (pin "1") (pinfunction "1_1") (pintype "passive"))
    )
    (net (code "62") (name "P5.0_SPIMOSI_J2.15") (class "Default")
      (node (ref "J2") (pin "15") (pinfunction "15_15") (pintype "bidirectional"))
      (node (ref "X1") (pin "3") (pinfunction "KL_3") (pintype "passive"))
    )
    (net (code "63") (name "P5.1_SPIMISO_J2.14") (class "Default")
      (node (ref "J2") (pin "14") (pinfunction "14_14") (pintype "bidirectional"))
      (node (ref "X1") (pin "5") (pinfunction "KL_5") (pintype "passive"))
    )
    (net (code "64") (name "P5.2_SPICLK_J1.7") (class "Default")
      (node (ref "J1") (pin "7") (pinfunction "7_7") (pintype "bidirectional"))
      (node (ref "X1") (pin "7") (pinfunction "KL_7") (pintype "passive"))
    )
    (net (code "65") (name "P5.3_IO_J2.17") (class "Default")
      (node (ref "J2") (pin "17") (pinfunction "17_17") (pintype "bidirectional"))
      (node (ref "X1") (pin "1") (pinfunction "KL_1") (pintype "passive"))
    )
    (net (code "66") (name "P5.7_PWM_J2.19") (class "Default")
      (node (ref "J2") (pin "19") (pinfunction "19_19") (pintype "bidirectional"))
    )
    (net (code "67") (name "P6.0_UTXD_J1.4") (class "Default")
      (node (ref "J1") (pin "4") (pinfunction "4_4") (pintype "bidirectional"))
      (node (ref "U$14") (pin "5") (pinfunction "KL_5") (pintype "passive"))
      (node (ref "U$16") (pin "4") (pinfunction "CATODE3_4") (pintype "passive"))
      (node (ref "U$9") (pin "P$3") (pinfunction "3_P$3") (pintype "passive"))
    )
    (net (code "68") (name "P6.1_URXD_J1.3") (class "Default")
      (node (ref "J1") (pin "3") (pinfunction "3_3") (pintype "bidirectional"))
      (node (ref "U$14") (pin "3") (pinfunction "KL_3") (pintype "passive"))
      (node (ref "U$16") (pin "6") (pinfunction "CATODE5_6") (pintype "passive"))
      (node (ref "U$9") (pin "P$4") (pinfunction "4_P$4") (pintype "passive"))
    )
    (net (code "69") (name "P6.2_IO_J1.5") (class "Default")
      (node (ref "J1") (pin "5") (pinfunction "5_5") (pintype "bidirectional"))
      (node (ref "U$14") (pin "6") (pinfunction "KL_6") (pintype "passive"))
      (node (ref "U$16") (pin "5") (pinfunction "CATODE4_5") (pintype "passive"))
    )
    (net (code "70") (name "P6.3_IO_J1.8") (class "Default")
      (node (ref "J1") (pin "8") (pinfunction "8_8") (pintype "bidirectional"))
      (node (ref "U$14") (pin "4") (pinfunction "KL_4") (pintype "passive"))
      (node (ref "U$16") (pin "1") (pinfunction "CATODE1_1") (pintype "passive"))
    )
    (net (code "71") (name "P7.0_I2CSDA_J1.10") (class "Default")
      (node (ref "J1") (pin "10") (pinfunction "10_10") (pintype "bidirectional"))
      (node (ref "R13") (pin "2") (pinfunction "2_2") (pintype "passive"))
      (node (ref "U$1") (pin "5") (pinfunction "SDA_5") (pintype "bidirectional"))
      (node (ref "X2") (pin "3") (pinfunction "KL_3") (pintype "passive"))
      (node (ref "X2") (pin "4") (pinfunction "KL_4") (pintype "passive"))
    )
    (net (code "72") (name "P7.1_I2CSCL_J1.9") (class "Default")
      (node (ref "J1") (pin "9") (pinfunction "9_9") (pintype "bidirectional"))
      (node (ref "R12") (pin "2") (pinfunction "2_2") (pintype "passive"))
      (node (ref "U$1") (pin "6") (pinfunction "SCL_6") (pintype "bidirectional"))
      (node (ref "X2") (pin "1") (pinfunction "KL_1") (pintype "passive"))
      (node (ref "X2") (pin "2") (pinfunction "KL_2") (pintype "passive"))
    )
    (net (code "73") (name "P7.3_CAPTURE_J4.36") (class "Default")
      (node (ref "J4") (pin "36") (pinfunction "36_36") (pintype "bidirectional"))
    )
    (net (code "74") (name "P8.0_IO_J3.30") (class "Default")
      (node (ref "J3") (pin "30") (pinfunction "30_30") (pintype "bidirectional"))
    )
    (net (code "75") (name "P8.1_IO_J2.11") (class "Default")
      (node (ref "J2") (pin "11") (pinfunction "11_11") (pintype "bidirectional"))
    )
    (net (code "76") (name "P8.2_IO_J2.12") (class "Default")
      (node (ref "J2") (pin "12") (pinfunction "12_12") (pintype "bidirectional"))
    )
    (net (code "77") (name "P8.3_IO_J2.13") (class "Default")
      (node (ref "J2") (pin "13") (pinfunction "13_13") (pintype "bidirectional"))
    )
    (net (code "78") (name "unconnected-(U$1-WP-Pad7)") (class "Default")
      (node (ref "U$1") (pin "7") (pinfunction "WP_7") (pintype "bidirectional"))
    )
    (net (code "79") (name "unconnected-(U$9-5-PadP$5)") (class "Default")
      (node (ref "U$9") (pin "P$5") (pinfunction "5_P$5") (pintype "passive"))
    )
    (net (code "80") (name "unconnected-(U$9-7-PadP$7)") (class "Default")
      (node (ref "U$9") (pin "P$7") (pinfunction "7_P$7") (pintype "passive"))
    )
    (net (code "81") (name "unconnected-(U$14A-KL-Pad1)") (class "Default")
      (node (ref "U$14") (pin "1") (pinfunction "KL_1") (pintype "passive"))
    )
    (net (code "82") (name "unconnected-(U$14N-KL-Pad7)") (class "Default")
      (node (ref "U$14") (pin "7") (pinfunction "KL_7") (pintype "passive"))
    )
    (net (code "83") (name "unconnected-(U$14O-KL-Pad8)") (class "Default")
      (node (ref "U$14") (pin "8") (pinfunction "KL_8") (pintype "passive"))
    )
    (net (code "84") (name "~{RST}{slash}SBWTDIO") (class "Default")
      (node (ref "J2") (pin "16") (pinfunction "16_16") (pintype "bidirectional"))
    )
  )
)
